# LEDs.net
KiCad netlist of a schematic drawn in Altium Designer
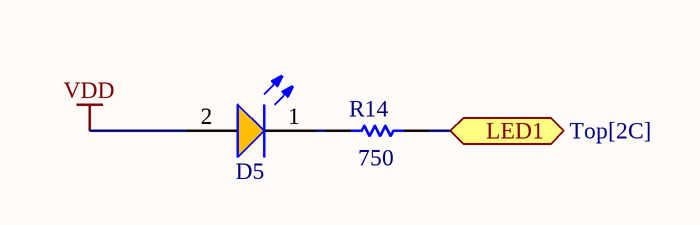
[diagram p0: LEDs.SchDoc]

(export (version "E")
  (design (tool "Eeschema 10.0.6"))
  (components
    (comp (ref "D5")
      (value "Amber, 2V, 120°")
      (footprint "WL-SMTW_3528")
      (description "WL-SMTW Mono-color TOP LED Waterclear, size 3528, Amber, 2V, 120°")
      (fields
        (field (name "MANUFACTURER PART NUMBER") "150141AS73100")
        (field (name "MANUFACTURER") "Wurth Elektronik")
      )
      (libsource (lib "missing_parts") (part "150141AS73100"))
    )
    (comp (ref "R14")
      (value "750")
      (footprint "R0402")
      (description "SMD Chip Resistor, 750 Ohm")
      (fields (field (name "MANUFACTURER") "Wurth") (field (name "MANUFACTURER PART NUMBER") "560112110262"))
      (libsource (lib "MCD_PARTS_database") (part "Resistor"))
    )
  )
  (nets
    (net (code "1") (name "/LED1") (class "Default")
      (node (ref "R14") (pin "2") (pinfunction "2_2") (pintype "passive"))
    )
    (net (code "2") (name "Net-(D5-K)") (class "Default")
      (node (ref "D5") (pin "1") (pinfunction "K_1") (pintype "passive"))
      (node (ref "R14") (pin "1") (pinfunction "1_1") (pintype "passive"))
    )
    (net (code "3") (name "VDD") (class "Default")
      (node (ref "D5") (pin "2") (pinfunction "A_2") (pintype "passive"))
    )
  )
)
